# FPGA_power.net
KiCad netlist of a schematic drawn in Altium Designer
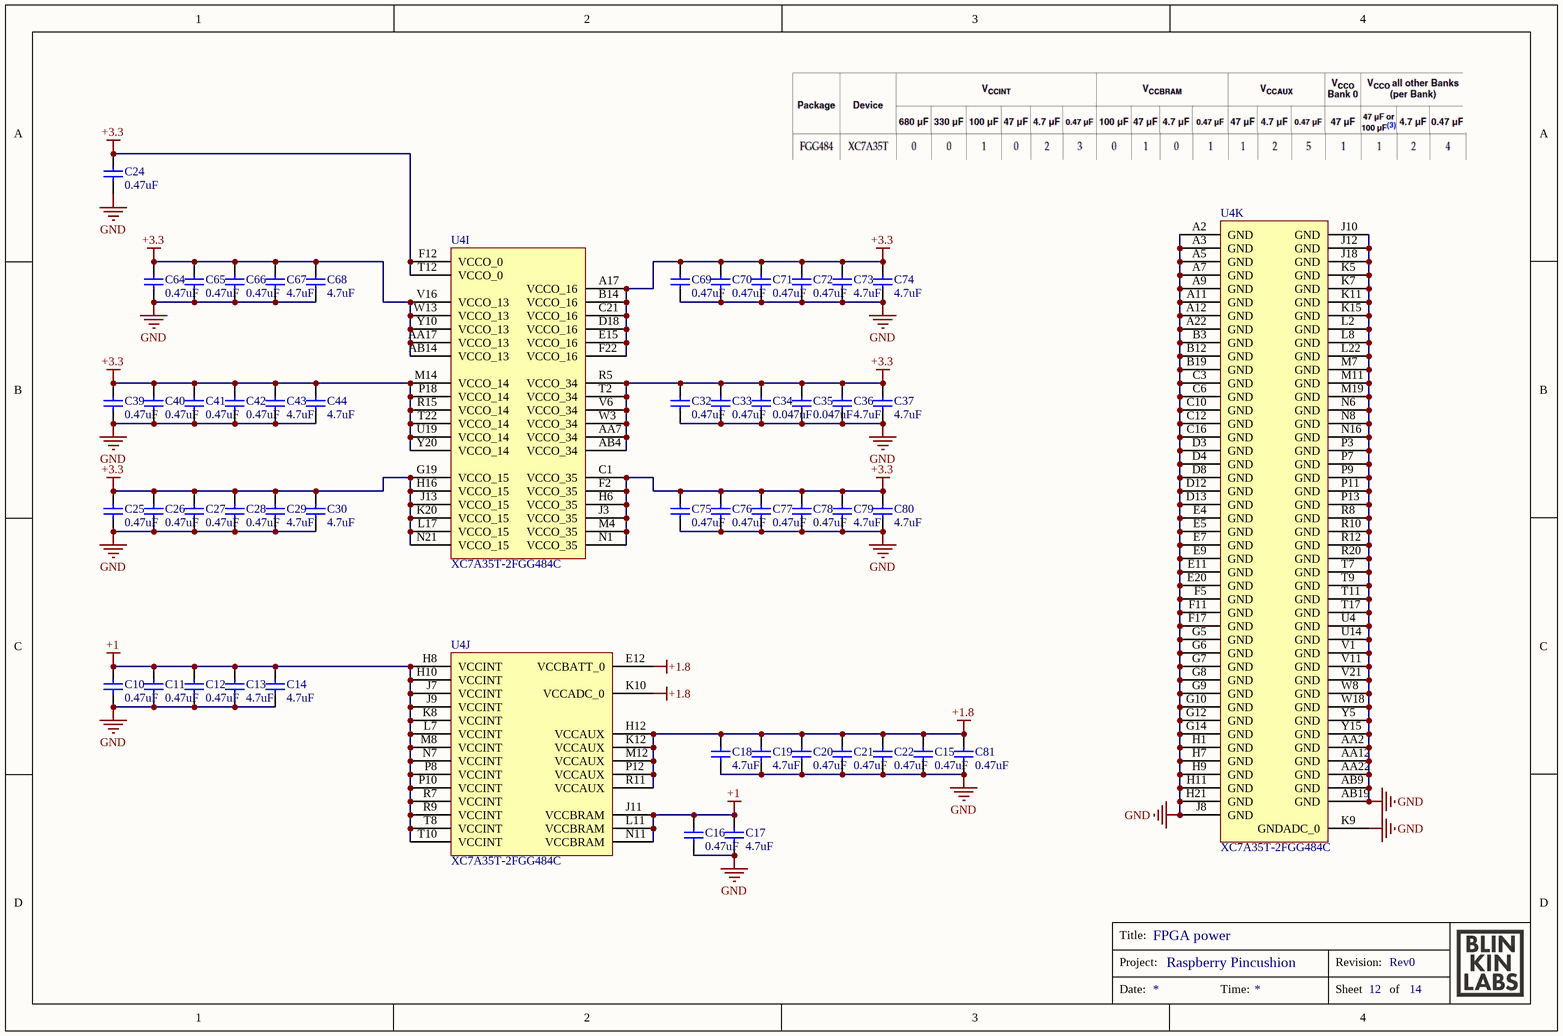
[diagram p0: FPGA power.SchDoc]

(export (version "E")
  (design (tool "Eeschema 10.0.6"))
  (components
    (comp (ref "C10")
      (value "0.47uF")
      (footprint "CAPC1005X06L")
      (description "CAP CER 0.47UF 6.3V X5R 0402")
      (fields
        (field (name "PARTNUMBER") "GRM155R60J474KE19D")
        (field (name "DIGI-KEY PART NUMBER") "490-3266-1-ND")
      )
      (libsource (lib "cap_murata") (part "CAPACITOR"))
    )
    (comp (ref "C11")
      (value "0.47uF")
      (footprint "CAPC1005X06L")
      (description "CAP CER 0.47UF 6.3V X5R 0402")
      (fields
        (field (name "PARTNUMBER") "GRM155R60J474KE19D")
        (field (name "DIGI-KEY PART NUMBER") "490-3266-1-ND")
      )
      (libsource (lib "cap_murata") (part "CAPACITOR"))
    )
    (comp (ref "C12")
      (value "0.47uF")
      (footprint "CAPC1005X06L")
      (description "CAP CER 0.47UF 6.3V X5R 0402")
      (fields
        (field (name "PARTNUMBER") "GRM155R60J474KE19D")
        (field (name "DIGI-KEY PART NUMBER") "490-3266-1-ND")
      )
      (libsource (lib "cap_murata") (part "CAPACITOR"))
    )
    (comp (ref "C13")
      (value "4.7uF")
      (footprint "CAPC1005X06L")
      (description "CAP CER 4.7UF 4V X5R 0402")
      (fields
        (field (name "PARTNUMBER") "GRM155R60G475ME47D")
        (field (name "DIGI-KEY PART NUMBER") "490-11980-1-ND")
      )
      (libsource (lib "cap_murata") (part "CAPACITOR"))
    )
    (comp (ref "C14")
      (value "4.7uF")
      (footprint "CAPC1005X06L")
      (description "CAP CER 4.7UF 4V X5R 0402")
      (fields
        (field (name "PARTNUMBER") "GRM155R60G475ME47D")
        (field (name "DIGI-KEY PART NUMBER") "490-11980-1-ND")
      )
      (libsource (lib "cap_murata") (part "CAPACITOR"))
    )
    (comp (ref "C15")
      (value "0.47uF")
      (footprint "CAPC1005X06L")
      (description "CAP CER 0.47UF 6.3V X5R 0402")
      (fields
        (field (name "PARTNUMBER") "GRM155R60J474KE19D")
        (field (name "DIGI-KEY PART NUMBER") "490-3266-1-ND")
      )
      (libsource (lib "cap_murata") (part "CAPACITOR"))
    )
    (comp (ref "C16")
      (value "0.47uF")
      (footprint "CAPC1005X06L")
      (description "CAP CER 0.47UF 6.3V X5R 0402")
      (fields
        (field (name "PARTNUMBER") "GRM155R60J474KE19D")
        (field (name "DIGI-KEY PART NUMBER") "490-3266-1-ND")
      )
      (libsource (lib "cap_murata") (part "CAPACITOR"))
    )
    (comp (ref "C17")
      (value "4.7uF")
      (footprint "CAPC1005X06L")
      (description "CAP CER 4.7UF 4V X5R 0402")
      (fields
        (field (name "PARTNUMBER") "GRM155R60G475ME47D")
        (field (name "DIGI-KEY PART NUMBER") "490-11980-1-ND")
      )
      (libsource (lib "cap_murata") (part "CAPACITOR"))
    )
    (comp (ref "C18")
      (value "4.7uF")
      (footprint "CAPC1005X06L")
      (description "CAP CER 4.7UF 4V X5R 0402")
      (fields
        (field (name "PARTNUMBER") "GRM155R60G475ME47D")
        (field (name "DIGI-KEY PART NUMBER") "490-11980-1-ND")
      )
      (libsource (lib "cap_murata") (part "CAPACITOR"))
    )
    (comp (ref "C19")
      (value "4.7uF")
      (footprint "CAPC1005X06L")
      (description "CAP CER 4.7UF 4V X5R 0402")
      (fields
        (field (name "PARTNUMBER") "GRM155R60G475ME47D")
        (field (name "DIGI-KEY PART NUMBER") "490-11980-1-ND")
      )
      (libsource (lib "cap_murata") (part "CAPACITOR"))
    )
    (comp (ref "C20")
      (value "0.47uF")
      (footprint "CAPC1005X06L")
      (description "CAP CER 0.47UF 6.3V X5R 0402")
      (fields
        (field (name "PARTNUMBER") "GRM155R60J474KE19D")
        (field (name "DIGI-KEY PART NUMBER") "490-3266-1-ND")
      )
      (libsource (lib "cap_murata") (part "CAPACITOR"))
    )
    (comp (ref "C21")
      (value "0.47uF")
      (footprint "CAPC1005X06L")
      (description "CAP CER 0.47UF 6.3V X5R 0402")
      (fields
        (field (name "PARTNUMBER") "GRM155R60J474KE19D")
        (field (name "DIGI-KEY PART NUMBER") "490-3266-1-ND")
      )
      (libsource (lib "cap_murata") (part "CAPACITOR"))
    )
    (comp (ref "C22")
      (value "0.47uF")
      (footprint "CAPC1005X06L")
      (description "CAP CER 0.47UF 6.3V X5R 0402")
      (fields
        (field (name "PARTNUMBER") "GRM155R60J474KE19D")
        (field (name "DIGI-KEY PART NUMBER") "490-3266-1-ND")
      )
      (libsource (lib "cap_murata") (part "CAPACITOR"))
    )
    (comp (ref "C24")
      (value "0.47uF")
      (footprint "CAPC1005X06L")
      (description "CAP CER 0.47UF 6.3V X5R 0402")
      (fields
        (field (name "PARTNUMBER") "GRM155R60J474KE19D")
        (field (name "DIGI-KEY PART NUMBER") "490-3266-1-ND")
      )
      (libsource (lib "cap_murata") (part "CAPACITOR"))
    )
    (comp (ref "C25")
      (value "0.47uF")
      (footprint "CAPC1005X06L")
      (description "CAP CER 0.47UF 6.3V X5R 0402")
      (fields
        (field (name "PARTNUMBER") "GRM155R60J474KE19D")
        (field (name "DIGI-KEY PART NUMBER") "490-3266-1-ND")
      )
      (libsource (lib "cap_murata") (part "CAPACITOR"))
    )
    (comp (ref "C26")
      (value "0.47uF")
      (footprint "CAPC1005X06L")
      (description "CAP CER 0.47UF 6.3V X5R 0402")
      (fields
        (field (name "PARTNUMBER") "GRM155R60J474KE19D")
        (field (name "DIGI-KEY PART NUMBER") "490-3266-1-ND")
      )
      (libsource (lib "cap_murata") (part "CAPACITOR"))
    )
    (comp (ref "C27")
      (value "0.47uF")
      (footprint "CAPC1005X06L")
      (description "CAP CER 0.47UF 6.3V X5R 0402")
      (fields
        (field (name "PARTNUMBER") "GRM155R60J474KE19D")
        (field (name "DIGI-KEY PART NUMBER") "490-3266-1-ND")
      )
      (libsource (lib "cap_murata") (part "CAPACITOR"))
    )
    (comp (ref "C28")
      (value "0.47uF")
      (footprint "CAPC1005X06L")
      (description "CAP CER 0.47UF 6.3V X5R 0402")
      (fields
        (field (name "PARTNUMBER") "GRM155R60J474KE19D")
        (field (name "DIGI-KEY PART NUMBER") "490-3266-1-ND")
      )
      (libsource (lib "cap_murata") (part "CAPACITOR"))
    )
    (comp (ref "C29")
      (value "4.7uF")
      (footprint "CAPC1005X06L")
      (description "CAP CER 4.7UF 4V X5R 0402")
      (fields
        (field (name "PARTNUMBER") "GRM155R60G475ME47D")
        (field (name "DIGI-KEY PART NUMBER") "490-11980-1-ND")
      )
      (libsource (lib "cap_murata") (part "CAPACITOR"))
    )
    (comp (ref "C30")
      (value "4.7uF")
      (footprint "CAPC1005X06L")
      (description "CAP CER 4.7UF 4V X5R 0402")
      (fields
        (field (name "PARTNUMBER") "GRM155R60G475ME47D")
        (field (name "DIGI-KEY PART NUMBER") "490-11980-1-ND")
      )
      (libsource (lib "cap_murata") (part "CAPACITOR"))
    )
    (comp (ref "C32")
      (value "0.47uF")
      (footprint "CAPC1005X06L")
      (description "CAP CER 0.47UF 6.3V X5R 0402")
      (fields
        (field (name "PARTNUMBER") "GRM155R60J474KE19D")
        (field (name "DIGI-KEY PART NUMBER") "490-3266-1-ND")
      )
      (libsource (lib "cap_murata") (part "CAPACITOR"))
    )
    (comp (ref "C33")
      (value "0.47uF")
      (footprint "CAPC1005X06L")
      (description "CAP CER 0.47UF 6.3V X5R 0402")
      (fields
        (field (name "PARTNUMBER") "GRM155R60J474KE19D")
        (field (name "DIGI-KEY PART NUMBER") "490-3266-1-ND")
      )
      (libsource (lib "cap_murata") (part "CAPACITOR"))
    )
    (comp (ref "C34")
      (value "0.047uF")
      (footprint "CAPC1005X06L")
      (description "CAP CER 0.047UF 6.3V X5R 0402")
      (fields
        (field (name "PARTNUMBER") "GRM155R60J473KA01D")
        (field (name "DIGI-KEY PART NUMBER") "490-8250-1-ND")
      )
      (libsource (lib "cap_murata") (part "CAPACITOR"))
    )
    (comp (ref "C35")
      (value "0.047uF")
      (footprint "CAPC1005X06L")
      (description "CAP CER 0.047UF 6.3V X5R 0402")
      (fields
        (field (name "PARTNUMBER") "GRM155R60J473KA01D")
        (field (name "DIGI-KEY PART NUMBER") "490-8250-1-ND")
      )
      (libsource (lib "cap_murata") (part "CAPACITOR"))
    )
    (comp (ref "C36")
      (value "4.7uF")
      (footprint "CAPC1005X06L")
      (description "CAP CER 4.7UF 4V X5R 0402")
      (fields
        (field (name "PARTNUMBER") "GRM155R60G475ME47D")
        (field (name "DIGI-KEY PART NUMBER") "490-11980-1-ND")
      )
      (libsource (lib "cap_murata") (part "CAPACITOR"))
    )
    (comp (ref "C37")
      (value "4.7uF")
      (footprint "CAPC1005X06L")
      (description "CAP CER 4.7UF 4V X5R 0402")
      (fields
        (field (name "PARTNUMBER") "GRM155R60G475ME47D")
        (field (name "DIGI-KEY PART NUMBER") "490-11980-1-ND")
      )
      (libsource (lib "cap_murata") (part "CAPACITOR"))
    )
    (comp (ref "C39")
      (value "0.47uF")
      (footprint "CAPC1005X06L")
      (description "CAP CER 0.47UF 6.3V X5R 0402")
      (fields
        (field (name "PARTNUMBER") "GRM155R60J474KE19D")
        (field (name "DIGI-KEY PART NUMBER") "490-3266-1-ND")
      )
      (libsource (lib "cap_murata") (part "CAPACITOR"))
    )
    (comp (ref "C40")
      (value "0.47uF")
      (footprint "CAPC1005X06L")
      (description "CAP CER 0.47UF 6.3V X5R 0402")
      (fields
        (field (name "PARTNUMBER") "GRM155R60J474KE19D")
        (field (name "DIGI-KEY PART NUMBER") "490-3266-1-ND")
      )
      (libsource (lib "cap_murata") (part "CAPACITOR"))
    )
    (comp (ref "C41")
      (value "0.47uF")
      (footprint "CAPC1005X06L")
      (description "CAP CER 0.47UF 6.3V X5R 0402")
      (fields
        (field (name "PARTNUMBER") "GRM155R60J474KE19D")
        (field (name "DIGI-KEY PART NUMBER") "490-3266-1-ND")
      )
      (libsource (lib "cap_murata") (part "CAPACITOR"))
    )
    (comp (ref "C42")
      (value "0.47uF")
      (footprint "CAPC1005X06L")
      (description "CAP CER 0.47UF 6.3V X5R 0402")
      (fields
        (field (name "PARTNUMBER") "GRM155R60J474KE19D")
        (field (name "DIGI-KEY PART NUMBER") "490-3266-1-ND")
      )
      (libsource (lib "cap_murata") (part "CAPACITOR"))
    )
    (comp (ref "C43")
      (value "4.7uF")
      (footprint "CAPC1005X06L")
      (description "CAP CER 4.7UF 4V X5R 0402")
      (fields
        (field (name "PARTNUMBER") "GRM155R60G475ME47D")
        (field (name "DIGI-KEY PART NUMBER") "490-11980-1-ND")
      )
      (libsource (lib "cap_murata") (part "CAPACITOR"))
    )
    (comp (ref "C44")
      (value "4.7uF")
      (footprint "CAPC1005X06L")
      (description "CAP CER 4.7UF 4V X5R 0402")
      (fields
        (field (name "PARTNUMBER") "GRM155R60G475ME47D")
        (field (name "DIGI-KEY PART NUMBER") "490-11980-1-ND")
      )
      (libsource (lib "cap_murata") (part "CAPACITOR"))
    )
    (comp (ref "C64")
      (value "0.47uF")
      (footprint "CAPC1005X06L")
      (description "CAP CER 0.47UF 6.3V X5R 0402")
      (fields
        (field (name "PARTNUMBER") "GRM155R60J474KE19D")
        (field (name "DIGI-KEY PART NUMBER") "490-3266-1-ND")
      )
      (libsource (lib "cap_murata") (part "CAPACITOR"))
    )
    (comp (ref "C65")
      (value "0.47uF")
      (footprint "CAPC1005X06L")
      (description "CAP CER 0.47UF 6.3V X5R 0402")
      (fields
        (field (name "PARTNUMBER") "GRM155R60J474KE19D")
        (field (name "DIGI-KEY PART NUMBER") "490-3266-1-ND")
      )
      (libsource (lib "cap_murata") (part "CAPACITOR"))
    )
    (comp (ref "C66")
      (value "0.47uF")
      (footprint "CAPC1005X06L")
      (description "CAP CER 0.47UF 6.3V X5R 0402")
      (fields
        (field (name "PARTNUMBER") "GRM155R60J474KE19D")
        (field (name "DIGI-KEY PART NUMBER") "490-3266-1-ND")
      )
      (libsource (lib "cap_murata") (part "CAPACITOR"))
    )
    (comp (ref "C67")
      (value "4.7uF")
      (footprint "CAPC1005X06L")
      (description "CAP CER 4.7UF 4V X5R 0402")
      (fields
        (field (name "PARTNUMBER") "GRM155R60G475ME47D")
        (field (name "DIGI-KEY PART NUMBER") "490-11980-1-ND")
      )
      (libsource (lib "cap_murata") (part "CAPACITOR"))
    )
    (comp (ref "C68")
      (value "4.7uF")
      (footprint "CAPC1005X06L")
      (description "CAP CER 4.7UF 4V X5R 0402")
      (fields
        (field (name "PARTNUMBER") "GRM155R60G475ME47D")
        (field (name "DIGI-KEY PART NUMBER") "490-11980-1-ND")
      )
      (libsource (lib "cap_murata") (part "CAPACITOR"))
    )
    (comp (ref "C69")
      (value "0.47uF")
      (footprint "CAPC1005X06L")
      (description "CAP CER 0.47UF 6.3V X5R 0402")
      (fields
        (field (name "PARTNUMBER") "GRM155R60J474KE19D")
        (field (name "DIGI-KEY PART NUMBER") "490-3266-1-ND")
      )
      (libsource (lib "cap_murata") (part "CAPACITOR"))
    )
    (comp (ref "C70")
      (value "0.47uF")
      (footprint "CAPC1005X06L")
      (description "CAP CER 0.47UF 6.3V X5R 0402")
      (fields
        (field (name "PARTNUMBER") "GRM155R60J474KE19D")
        (field (name "DIGI-KEY PART NUMBER") "490-3266-1-ND")
      )
      (libsource (lib "cap_murata") (part "CAPACITOR"))
    )
    (comp (ref "C71")
      (value "0.47uF")
      (footprint "CAPC1005X06L")
      (description "CAP CER 0.47UF 6.3V X5R 0402")
      (fields
        (field (name "PARTNUMBER") "GRM155R60J474KE19D")
        (field (name "DIGI-KEY PART NUMBER") "490-3266-1-ND")
      )
      (libsource (lib "cap_murata") (part "CAPACITOR"))
    )
    (comp (ref "C72")
      (value "0.47uF")
      (footprint "CAPC1005X06L")
      (description "CAP CER 0.47UF 6.3V X5R 0402")
      (fields
        (field (name "PARTNUMBER") "GRM155R60J474KE19D")
        (field (name "DIGI-KEY PART NUMBER") "490-3266-1-ND")
      )
      (libsource (lib "cap_murata") (part "CAPACITOR"))
    )
    (comp (ref "C73")
      (value "4.7uF")
      (footprint "CAPC1005X06L")
      (description "CAP CER 4.7UF 4V X5R 0402")
      (fields
        (field (name "PARTNUMBER") "GRM155R60G475ME47D")
        (field (name "DIGI-KEY PART NUMBER") "490-11980-1-ND")
      )
      (libsource (lib "cap_murata") (part "CAPACITOR"))
    )
    (comp (ref "C74")
      (value "4.7uF")
      (footprint "CAPC1005X06L")
      (description "CAP CER 4.7UF 4V X5R 0402")
      (fields
        (field (name "PARTNUMBER") "GRM155R60G475ME47D")
        (field (name "DIGI-KEY PART NUMBER") "490-11980-1-ND")
      )
      (libsource (lib "cap_murata") (part "CAPACITOR"))
    )
    (comp (ref "C75")
      (value "0.47uF")
      (footprint "CAPC1005X06L")
      (description "CAP CER 0.47UF 6.3V X5R 0402")
      (fields
        (field (name "PARTNUMBER") "GRM155R60J474KE19D")
        (field (name "DIGI-KEY PART NUMBER") "490-3266-1-ND")
      )
      (libsource (lib "cap_murata") (part "CAPACITOR"))
    )
    (comp (ref "C76")
      (value "0.47uF")
      (footprint "CAPC1005X06L")
      (description "CAP CER 0.47UF 6.3V X5R 0402")
      (fields
        (field (name "PARTNUMBER") "GRM155R60J474KE19D")
        (field (name "DIGI-KEY PART NUMBER") "490-3266-1-ND")
      )
      (libsource (lib "cap_murata") (part "CAPACITOR"))
    )
    (comp (ref "C77")
      (value "0.47uF")
      (footprint "CAPC1005X06L")
      (description "CAP CER 0.47UF 6.3V X5R 0402")
      (fields
        (field (name "PARTNUMBER") "GRM155R60J474KE19D")
        (field (name "DIGI-KEY PART NUMBER") "490-3266-1-ND")
      )
      (libsource (lib "cap_murata") (part "CAPACITOR"))
    )
    (comp (ref "C78")
      (value "0.47uF")
      (footprint "CAPC1005X06L")
      (description "CAP CER 0.47UF 6.3V X5R 0402")
      (fields
        (field (name "PARTNUMBER") "GRM155R60J474KE19D")
        (field (name "DIGI-KEY PART NUMBER") "490-3266-1-ND")
      )
      (libsource (lib "cap_murata") (part "CAPACITOR"))
    )
    (comp (ref "C79")
      (value "4.7uF")
      (footprint "CAPC1005X06L")
      (description "CAP CER 4.7UF 4V X5R 0402")
      (fields
        (field (name "PARTNUMBER") "GRM155R60G475ME47D")
        (field (name "DIGI-KEY PART NUMBER") "490-11980-1-ND")
      )
      (libsource (lib "cap_murata") (part "CAPACITOR"))
    )
    (comp (ref "C80")
      (value "4.7uF")
      (footprint "CAPC1005X06L")
      (description "CAP CER 4.7UF 4V X5R 0402")
      (fields
        (field (name "PARTNUMBER") "GRM155R60G475ME47D")
        (field (name "DIGI-KEY PART NUMBER") "490-11980-1-ND")
      )
      (libsource (lib "cap_murata") (part "CAPACITOR"))
    )
    (comp (ref "C81")
      (value "0.47uF")
      (footprint "CAPC1005X06L")
      (description "CAP CER 0.47UF 6.3V X5R 0402")
      (fields
        (field (name "PARTNUMBER") "GRM155R60J474KE19D")
        (field (name "DIGI-KEY PART NUMBER") "490-3266-1-ND")
      )
      (libsource (lib "cap_murata") (part "CAPACITOR"))
    )
    (comp (ref "U4")
      (value "XC7A35T-2FGG484C")
      (footprint "FGG484")
      (description "Artix-7 FPGA, 250 User I/Os, 4 GTP, 484-Ball BGA, Speed Grade 2, Commercial Grade, Pb-Free")
      (fields (field (name "MANUFACTURER") "Xilinx"))
      (libsource (lib "Altium Content Vault") (part "XLNX-XC7A35T-FGG484"))
    )
  )
  (nets
    (net (code "1") (name "+1") (class "Default")
      (node (ref "C10") (pin "1") (pinfunction "1_1") (pintype "passive"))
      (node (ref "C11") (pin "1") (pinfunction "1_1") (pintype "passive"))
      (node (ref "C12") (pin "1") (pinfunction "1_1") (pintype "passive"))
      (node (ref "C13") (pin "2") (pinfunction "2_2") (pintype "passive"))
      (node (ref "C14") (pin "2") (pinfunction "2_2") (pintype "passive"))
      (node (ref "C16") (pin "1") (pinfunction "1_1") (pintype "passive"))
      (node (ref "C17") (pin "2") (pinfunction "2_2") (pintype "passive"))
      (node (ref "U4") (pin "H10") (pinfunction "VCCINT_H10") (pintype "power_in"))
      (node (ref "U4") (pin "H8") (pinfunction "VCCINT_H8") (pintype "power_in"))
      (node (ref "U4") (pin "J11") (pinfunction "VCCBRAM_J11") (pintype "power_in"))
      (node (ref "U4") (pin "J7") (pinfunction "VCCINT_J7") (pintype "power_in"))
      (node (ref "U4") (pin "J9") (pinfunction "VCCINT_J9") (pintype "power_in"))
      (node (ref "U4") (pin "K8") (pinfunction "VCCINT_K8") (pintype "power_in"))
      (node (ref "U4") (pin "L11") (pinfunction "VCCBRAM_L11") (pintype "power_in"))
      (node (ref "U4") (pin "L7") (pinfunction "VCCINT_L7") (pintype "power_in"))
      (node (ref "U4") (pin "M8") (pinfunction "VCCINT_M8") (pintype "power_in"))
      (node (ref "U4") (pin "N11") (pinfunction "VCCBRAM_N11") (pintype "power_in"))
      (node (ref "U4") (pin "N7") (pinfunction "VCCINT_N7") (pintype "power_in"))
      (node (ref "U4") (pin "P10") (pinfunction "VCCINT_P10") (pintype "power_in"))
      (node (ref "U4") (pin "P8") (pinfunction "VCCINT_P8") (pintype "power_in"))
      (node (ref "U4") (pin "R7") (pinfunction "VCCINT_R7") (pintype "power_in"))
      (node (ref "U4") (pin "R9") (pinfunction "VCCINT_R9") (pintype "power_in"))
      (node (ref "U4") (pin "T10") (pinfunction "VCCINT_T10") (pintype "power_in"))
      (node (ref "U4") (pin "T8") (pinfunction "VCCINT_T8") (pintype "power_in"))
    )
    (net (code "2") (name "+1.8") (class "Default")
      (node (ref "C15") (pin "1") (pinfunction "1_1") (pintype "passive"))
      (node (ref "C18") (pin "2") (pinfunction "2_2") (pintype "passive"))
      (node (ref "C19") (pin "2") (pinfunction "2_2") (pintype "passive"))
      (node (ref "C20") (pin "1") (pinfunction "1_1") (pintype "passive"))
      (node (ref "C21") (pin "1") (pinfunction "1_1") (pintype "passive"))
      (node (ref "C22") (pin "1") (pinfunction "1_1") (pintype "passive"))
      (node (ref "C81") (pin "1") (pinfunction "1_1") (pintype "passive"))
      (node (ref "U4") (pin "E12") (pinfunction "VCCBATT_0_E12") (pintype "power_in"))
      (node (ref "U4") (pin "H12") (pinfunction "VCCAUX_H12") (pintype "power_in"))
      (node (ref "U4") (pin "K10") (pinfunction "VCCADC_0_K10") (pintype "power_in"))
      (node (ref "U4") (pin "K12") (pinfunction "VCCAUX_K12") (pintype "power_in"))
      (node (ref "U4") (pin "M12") (pinfunction "VCCAUX_M12") (pintype "power_in"))
      (node (ref "U4") (pin "P12") (pinfunction "VCCAUX_P12") (pintype "power_in"))
      (node (ref "U4") (pin "R11") (pinfunction "VCCAUX_R11") (pintype "power_in"))
    )
    (net (code "3") (name "+3.3") (class "Default")
      (node (ref "C24") (pin "1") (pinfunction "1_1") (pintype "passive"))
      (node (ref "C25") (pin "1") (pinfunction "1_1") (pintype "passive"))
      (node (ref "C26") (pin "1") (pinfunction "1_1") (pintype "passive"))
      (node (ref "C27") (pin "1") (pinfunction "1_1") (pintype "passive"))
      (node (ref "C28") (pin "1") (pinfunction "1_1") (pintype "passive"))
      (node (ref "C29") (pin "2") (pinfunction "2_2") (pintype "passive"))
      (node (ref "C30") (pin "2") (pinfunction "2_2") (pintype "passive"))
      (node (ref "C32") (pin "1") (pinfunction "1_1") (pintype "passive"))
      (node (ref "C33") (pin "1") (pinfunction "1_1") (pintype "passive"))
      (node (ref "C34") (pin "1") (pinfunction "1_1") (pintype "passive"))
      (node (ref "C35") (pin "1") (pinfunction "1_1") (pintype "passive"))
      (node (ref "C36") (pin "2") (pinfunction "2_2") (pintype "passive"))
      (node (ref "C37") (pin "2") (pinfunction "2_2") (pintype "passive"))
      (node (ref "C39") (pin "1") (pinfunction "1_1") (pintype "passive"))
      (node (ref "C40") (pin "1") (pinfunction "1_1") (pintype "passive"))
      (node (ref "C41") (pin "1") (pinfunction "1_1") (pintype "passive"))
      (node (ref "C42") (pin "1") (pinfunction "1_1") (pintype "passive"))
      (node (ref "C43") (pin "2") (pinfunction "2_2") (pintype "passive"))
      (node (ref "C44") (pin "2") (pinfunction "2_2") (pintype "passive"))
      (node (ref "C64") (pin "1") (pinfunction "1_1") (pintype "passive"))
      (node (ref "C65") (pin "1") (pinfunction "1_1") (pintype "passive"))
      (node (ref "C66") (pin "1") (pinfunction "1_1") (pintype "passive"))
      (node (ref "C67") (pin "2") (pinfunction "2_2") (pintype "passive"))
      (node (ref "C68") (pin "2") (pinfunction "2_2") (pintype "passive"))
      (node (ref "C69") (pin "1") (pinfunction "1_1") (pintype "passive"))
      (node (ref "C70") (pin "1") (pinfunction "1_1") (pintype "passive"))
      (node (ref "C71") (pin "1") (pinfunction "1_1") (pintype "passive"))
      (node (ref "C72") (pin "1") (pinfunction "1_1") (pintype "passive"))
      (node (ref "C73") (pin "2") (pinfunction "2_2") (pintype "passive"))
      (node (ref "C74") (pin "2") (pinfunction "2_2") (pintype "passive"))
      (node (ref "C75") (pin "1") (pinfunction "1_1") (pintype "passive"))
      (node (ref "C76") (pin "1") (pinfunction "1_1") (pintype "passive"))
      (node (ref "C77") (pin "1") (pinfunction "1_1") (pintype "passive"))
      (node (ref "C78") (pin "1") (pinfunction "1_1") (pintype "passive"))
      (node (ref "C79") (pin "2") (pinfunction "2_2") (pintype "passive"))
      (node (ref "C80") (pin "2") (pinfunction "2_2") (pintype "passive"))
      (node (ref "U4") (pin "A17") (pinfunction "VCCO_16_A17") (pintype "power_in"))
      (node (ref "U4") (pin "AA17") (pinfunction "VCCO_13_AA17") (pintype "power_in"))
      (node (ref "U4") (pin "AA7") (pinfunction "VCCO_34_AA7") (pintype "power_in"))
      (node (ref "U4") (pin "AB14") (pinfunction "VCCO_13_AB14") (pintype "power_in"))
      (node (ref "U4") (pin "AB4") (pinfunction "VCCO_34_AB4") (pintype "power_in"))
      (node (ref "U4") (pin "B14") (pinfunction "VCCO_16_B14") (pintype "power_in"))
      (node (ref "U4") (pin "C1") (pinfunction "VCCO_35_C1") (pintype "power_in"))
      (node (ref "U4") (pin "C21") (pinfunction "VCCO_16_C21") (pintype "power_in"))
      (node (ref "U4") (pin "D18") (pinfunction "VCCO_16_D18") (pintype "power_in"))
      (node (ref "U4") (pin "E15") (pinfunction "VCCO_16_E15") (pintype "power_in"))
      (node (ref "U4") (pin "F12") (pinfunction "VCCO_0_F12") (pintype "power_in"))
      (node (ref "U4") (pin "F2") (pinfunction "VCCO_35_F2") (pintype "power_in"))
      (node (ref "U4") (pin "F22") (pinfunction "VCCO_16_F22") (pintype "power_in"))
      (node (ref "U4") (pin "G19") (pinfunction "VCCO_15_G19") (pintype "power_in"))
      (node (ref "U4") (pin "H16") (pinfunction "VCCO_15_H16") (pintype "power_in"))
      (node (ref "U4") (pin "H6") (pinfunction "VCCO_35_H6") (pintype "power_in"))
      (node (ref "U4") (pin "J13") (pinfunction "VCCO_15_J13") (pintype "power_in"))
      (node (ref "U4") (pin "J3") (pinfunction "VCCO_35_J3") (pintype "power_in"))
      (node (ref "U4") (pin "K20") (pinfunction "VCCO_15_K20") (pintype "power_in"))
      (node (ref "U4") (pin "L17") (pinfunction "VCCO_15_L17") (pintype "power_in"))
      (node (ref "U4") (pin "M14") (pinfunction "VCCO_14_M14") (pintype "power_in"))
      (node (ref "U4") (pin "M4") (pinfunction "VCCO_35_M4") (pintype "power_in"))
      (node (ref "U4") (pin "N1") (pinfunction "VCCO_35_N1") (pintype "power_in"))
      (node (ref "U4") (pin "N21") (pinfunction "VCCO_15_N21") (pintype "power_in"))
      (node (ref "U4") (pin "P18") (pinfunction "VCCO_14_P18") (pintype "power_in"))
      (node (ref "U4") (pin "R15") (pinfunction "VCCO_14_R15") (pintype "power_in"))
      (node (ref "U4") (pin "R5") (pinfunction "VCCO_34_R5") (pintype "power_in"))
      (node (ref "U4") (pin "T12") (pinfunction "VCCO_0_T12") (pintype "power_in"))
      (node (ref "U4") (pin "T2") (pinfunction "VCCO_34_T2") (pintype "power_in"))
      (node (ref "U4") (pin "T22") (pinfunction "VCCO_14_T22") (pintype "power_in"))
      (node (ref "U4") (pin "U19") (pinfunction "VCCO_14_U19") (pintype "power_in"))
      (node (ref "U4") (pin "V16") (pinfunction "VCCO_13_V16") (pintype "power_in"))
      (node (ref "U4") (pin "V6") (pinfunction "VCCO_34_V6") (pintype "power_in"))
      (node (ref "U4") (pin "W13") (pinfunction "VCCO_13_W13") (pintype "power_in"))
      (node (ref "U4") (pin "W3") (pinfunction "VCCO_34_W3") (pintype "power_in"))
      (node (ref "U4") (pin "Y10") (pinfunction "VCCO_13_Y10") (pintype "power_in"))
      (node (ref "U4") (pin "Y20") (pinfunction "VCCO_14_Y20") (pintype "power_in"))
    )
    (net (code "4") (name "GND") (class "Default")
      (node (ref "C10") (pin "2") (pinfunction "2_2") (pintype "passive"))
      (node (ref "C11") (pin "2") (pinfunction "2_2") (pintype "passive"))
      (node (ref "C12") (pin "2") (pinfunction "2_2") (pintype "passive"))
      (node (ref "C13") (pin "1") (pinfunction "1_1") (pintype "passive"))
      (node (ref "C14") (pin "1") (pinfunction "1_1") (pintype "passive"))
      (node (ref "C15") (pin "2") (pinfunction "2_2") (pintype "passive"))
      (node (ref "C16") (pin "2") (pinfunction "2_2") (pintype "passive"))
      (node (ref "C17") (pin "1") (pinfunction "1_1") (pintype "passive"))
      (node (ref "C18") (pin "1") (pinfunction "1_1") (pintype "passive"))
      (node (ref "C19") (pin "1") (pinfunction "1_1") (pintype "passive"))
      (node (ref "C20") (pin "2") (pinfunction "2_2") (pintype "passive"))
      (node (ref "C21") (pin "2") (pinfunction "2_2") (pintype "passive"))
      (node (ref "C22") (pin "2") (pinfunction "2_2") (pintype "passive"))
      (node (ref "C24") (pin "2") (pinfunction "2_2") (pintype "passive"))
      (node (ref "C25") (pin "2") (pinfunction "2_2") (pintype "passive"))
      (node (ref "C26") (pin "2") (pinfunction "2_2") (pintype "passive"))
      (node (ref "C27") (pin "2") (pinfunction "2_2") (pintype "passive"))
      (node (ref "C28") (pin "2") (pinfunction "2_2") (pintype "passive"))
      (node (ref "C29") (pin "1") (pinfunction "1_1") (pintype "passive"))
      (node (ref "C30") (pin "1") (pinfunction "1_1") (pintype "passive"))
      (node (ref "C32") (pin "2") (pinfunction "2_2") (pintype "passive"))
      (node (ref "C33") (pin "2") (pinfunction "2_2") (pintype "passive"))
      (node (ref "C34") (pin "2") (pinfunction "2_2") (pintype "passive"))
      (node (ref "C35") (pin "2") (pinfunction "2_2") (pintype "passive"))
      (node (ref "C36") (pin "1") (pinfunction "1_1") (pintype "passive"))
      (node (ref "C37") (pin "1") (pinfunction "1_1") (pintype "passive"))
      (node (ref "C39") (pin "2") (pinfunction "2_2") (pintype "passive"))
      (node (ref "C40") (pin "2") (pinfunction "2_2") (pintype "passive"))
      (node (ref "C41") (pin "2") (pinfunction "2_2") (pintype "passive"))
      (node (ref "C42") (pin "2") (pinfunction "2_2") (pintype "passive"))
      (node (ref "C43") (pin "1") (pinfunction "1_1") (pintype "passive"))
      (node (ref "C44") (pin "1") (pinfunction "1_1") (pintype "passive"))
      (node (ref "C64") (pin "2") (pinfunction "2_2") (pintype "passive"))
      (node (ref "C65") (pin "2") (pinfunction "2_2") (pintype "passive"))
      (node (ref "C66") (pin "2") (pinfunction "2_2") (pintype "passive"))
      (node (ref "C67") (pin "1") (pinfunction "1_1") (pintype "passive"))
      (node (ref "C68") (pin "1") (pinfunction "1_1") (pintype "passive"))
      (node (ref "C69") (pin "2") (pinfunction "2_2") (pintype "passive"))
      (node (ref "C70") (pin "2") (pinfunction "2_2") (pintype "passive"))
      (node (ref "C71") (pin "2") (pinfunction "2_2") (pintype "passive"))
      (node (ref "C72") (pin "2") (pinfunction "2_2") (pintype "passive"))
      (node (ref "C73") (pin "1") (pinfunction "1_1") (pintype "passive"))
      (node (ref "C74") (pin "1") (pinfunction "1_1") (pintype "passive"))
      (node (ref "C75") (pin "2") (pinfunction "2_2") (pintype "passive"))
      (node (ref "C76") (pin "2") (pinfunction "2_2") (pintype "passive"))
      (node (ref "C77") (pin "2") (pinfunction "2_2") (pintype "passive"))
      (node (ref "C78") (pin "2") (pinfunction "2_2") (pintype "passive"))
      (node (ref "C79") (pin "1") (pinfunction "1_1") (pintype "passive"))
      (node (ref "C80") (pin "1") (pinfunction "1_1") (pintype "passive"))
      (node (ref "C81") (pin "2") (pinfunction "2_2") (pintype "passive"))
      (node (ref "U4") (pin "A11") (pinfunction "GND_A11") (pintype "power_in"))
      (node (ref "U4") (pin "A12") (pinfunction "GND_A12") (pintype "power_in"))
      (node (ref "U4") (pin "A2") (pinfunction "GND_A2") (pintype "power_in"))
      (node (ref "U4") (pin "A22") (pinfunction "GND_A22") (pintype "power_in"))
      (node (ref "U4") (pin "A3") (pinfunction "GND_A3") (pintype "power_in"))
      (node (ref "U4") (pin "A5") (pinfunction "GND_A5") (pintype "power_in"))
      (node (ref "U4") (pin "A7") (pinfunction "GND_A7") (pintype "power_in"))
      (node (ref "U4") (pin "A9") (pinfunction "GND_A9") (pintype "power_in"))
      (node (ref "U4") (pin "AA12") (pinfunction "GND_AA12") (pintype "power_in"))
      (node (ref "U4") (pin "AA2") (pinfunction "GND_AA2") (pintype "power_in"))
      (node (ref "U4") (pin "AA22") (pinfunction "GND_AA22") (pintype "power_in"))
      (node (ref "U4") (pin "AB19") (pinfunction "GND_AB19") (pintype "power_in"))
      (node (ref "U4") (pin "AB9") (pinfunction "GND_AB9") (pintype "power_in"))
      (node (ref "U4") (pin "B12") (pinfunction "GND_B12") (pintype "power_in"))
      (node (ref "U4") (pin "B19") (pinfunction "GND_B19") (pintype "power_in"))
      (node (ref "U4") (pin "B3") (pinfunction "GND_B3") (pintype "power_in"))
      (node (ref "U4") (pin "C10") (pinfunction "GND_C10") (pintype "power_in"))
      (node (ref "U4") (pin "C12") (pinfunction "GND_C12") (pintype "power_in"))
      (node (ref "U4") (pin "C16") (pinfunction "GND_C16") (pintype "power_in"))
      (node (ref "U4") (pin "C3") (pinfunction "GND_C3") (pintype "power_in"))
      (node (ref "U4") (pin "C6") (pinfunction "GND_C6") (pintype "power_in"))
      (node (ref "U4") (pin "D12") (pinfunction "GND_D12") (pintype "power_in"))
      (node (ref "U4") (pin "D13") (pinfunction "GND_D13") (pintype "power_in"))
      (node (ref "U4") (pin "D3") (pinfunction "GND_D3") (pintype "power_in"))
      (node (ref "U4") (pin "D4") (pinfunction "GND_D4") (pintype "power_in"))
      (node (ref "U4") (pin "D8") (pinfunction "GND_D8") (pintype "power_in"))
      (node (ref "U4") (pin "E11") (pinfunction "GND_E11") (pintype "power_in"))
      (node (ref "U4") (pin "E20") (pinfunction "GND_E20") (pintype "power_in"))
      (node (ref "U4") (pin "E4") (pinfunction "GND_E4") (pintype "power_in"))
      (node (ref "U4") (pin "E5") (pinfunction "GND_E5") (pintype "power_in"))
      (node (ref "U4") (pin "E7") (pinfunction "GND_E7") (pintype "power_in"))
      (node (ref "U4") (pin "E9") (pinfunction "GND_E9") (pintype "power_in"))
      (node (ref "U4") (pin "F11") (pinfunction "GND_F11") (pintype "power_in"))
      (node (ref "U4") (pin "F17") (pinfunction "GND_F17") (pintype "power_in"))
      (node (ref "U4") (pin "F5") (pinfunction "GND_F5") (pintype "power_in"))
      (node (ref "U4") (pin "G10") (pinfunction "GND_G10") (pintype "power_in"))
      (node (ref "U4") (pin "G12") (pinfunction "GND_G12") (pintype "power_in"))
      (node (ref "U4") (pin "G14") (pinfunction "GND_G14") (pintype "power_in"))
      (node (ref "U4") (pin "G5") (pinfunction "GND_G5") (pintype "power_in"))
      (node (ref "U4") (pin "G6") (pinfunction "GND_G6") (pintype "power_in"))
      (node (ref "U4") (pin "G7") (pinfunction "GND_G7") (pintype "power_in"))
      (node (ref "U4") (pin "G8") (pinfunction "GND_G8") (pintype "power_in"))
      (node (ref "U4") (pin "G9") (pinfunction "GND_G9") (pintype "power_in"))
      (node (ref "U4") (pin "H1") (pinfunction "GND_H1") (pintype "power_in"))
      (node (ref "U4") (pin "H11") (pinfunction "GND_H11") (pintype "power_in"))
      (node (ref "U4") (pin "H21") (pinfunction "GND_H21") (pintype "power_in"))
      (node (ref "U4") (pin "H7") (pinfunction "GND_H7") (pintype "power_in"))
      (node (ref "U4") (pin "H9") (pinfunction "GND_H9") (pintype "power_in"))
      (node (ref "U4") (pin "J10") (pinfunction "GND_J10") (pintype "power_in"))
      (node (ref "U4") (pin "J12") (pinfunction "GND_J12") (pintype "power_in"))
      (node (ref "U4") (pin "J18") (pinfunction "GND_J18") (pintype "power_in"))
      (node (ref "U4") (pin "J8") (pinfunction "GND_J8") (pintype "power_in"))
      (node (ref "U4") (pin "K11") (pinfunction "GND_K11") (pintype "power_in"))
      (node (ref "U4") (pin "K15") (pinfunction "GND_K15") (pintype "power_in"))
      (node (ref "U4") (pin "K5") (pinfunction "GND_K5") (pintype "power_in"))
      (node (ref "U4") (pin "K7") (pinfunction "GND_K7") (pintype "power_in"))
      (node (ref "U4") (pin "K9") (pinfunction "GNDADC_0_K9") (pintype "power_in"))
      (node (ref "U4") (pin "L2") (pinfunction "GND_L2") (pintype "power_in"))
      (node (ref "U4") (pin "L22") (pinfunction "GND_L22") (pintype "power_in"))
      (node (ref "U4") (pin "L8") (pinfunction "GND_L8") (pintype "power_in"))
      (node (ref "U4") (pin "M11") (pinfunction "GND_M11") (pintype "power_in"))
      (node (ref "U4") (pin "M19") (pinfunction "GND_M19") (pintype "power_in"))
      (node (ref "U4") (pin "M7") (pinfunction "GND_M7") (pintype "power_in"))
      (node (ref "U4") (pin "N16") (pinfunction "GND_N16") (pintype "power_in"))
      (node (ref "U4") (pin "N6") (pinfunction "GND_N6") (pintype "power_in"))
      (node (ref "U4") (pin "N8") (pinfunction "GND_N8") (pintype "power_in"))
      (node (ref "U4") (pin "P11") (pinfunction "GND_P11") (pintype "power_in"))
      (node (ref "U4") (pin "P13") (pinfunction "GND_P13") (pintype "power_in"))
      (node (ref "U4") (pin "P3") (pinfunction "GND_P3") (pintype "power_in"))
      (node (ref "U4") (pin "P7") (pinfunction "GND_P7") (pintype "power_in"))
      (node (ref "U4") (pin "P9") (pinfunction "GND_P9") (pintype "power_in"))
      (node (ref "U4") (pin "R10") (pinfunction "GND_R10") (pintype "power_in"))
      (node (ref "U4") (pin "R12") (pinfunction "GND_R12") (pintype "power_in"))
      (node (ref "U4") (pin "R20") (pinfunction "GND_R20") (pintype "power_in"))
      (node (ref "U4") (pin "R8") (pinfunction "GND_R8") (pintype "power_in"))
      (node (ref "U4") (pin "T11") (pinfunction "GND_T11") (pintype "power_in"))
      (node (ref "U4") (pin "T17") (pinfunction "GND_T17") (pintype "power_in"))
      (node (ref "U4") (pin "T7") (pinfunction "GND_T7") (pintype "power_in"))
      (node (ref "U4") (pin "T9") (pinfunction "GND_T9") (pintype "power_in"))
      (node (ref "U4") (pin "U14") (pinfunction "GND_U14") (pintype "power_in"))
      (node (ref "U4") (pin "U4") (pinfunction "GND_U4") (pintype "power_in"))
      (node (ref "U4") (pin "V1") (pinfunction "GND_V1") (pintype "power_in"))
      (node (ref "U4") (pin "V11") (pinfunction "GND_V11") (pintype "power_in"))
      (node (ref "U4") (pin "V21") (pinfunction "GND_V21") (pintype "power_in"))
      (node (ref "U4") (pin "W18") (pinfunction "GND_W18") (pintype "power_in"))
      (node (ref "U4") (pin "W8") (pinfunction "GND_W8") (pintype "power_in"))
      (node (ref "U4") (pin "Y15") (pinfunction "GND_Y15") (pintype "power_in"))
      (node (ref "U4") (pin "Y5") (pinfunction "GND_Y5") (pintype "power_in"))
    )
  )
)
